# sram_rom_old.net
KiCad netlist of a schematic drawn in Altium Designer
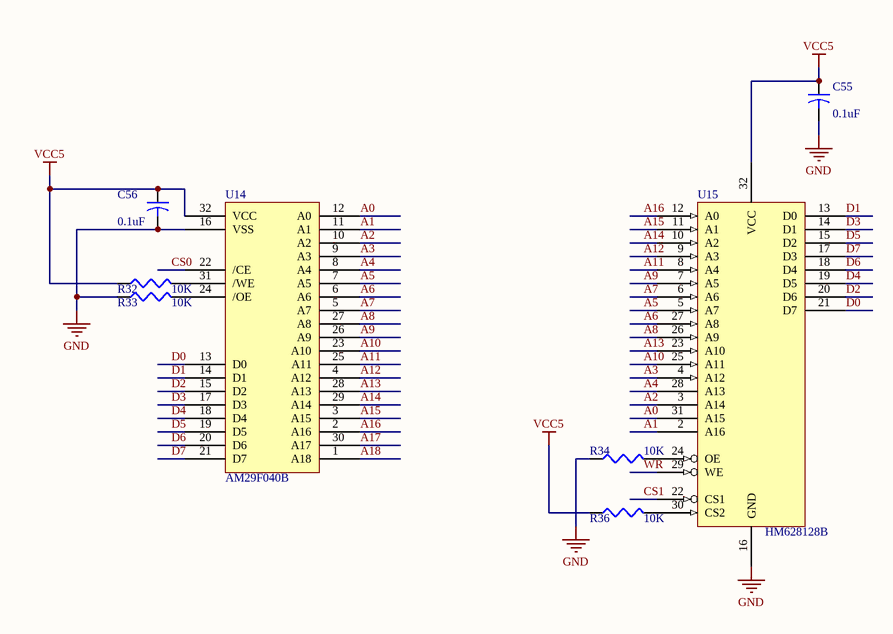
[diagram p0: sram_rom_old.SchDoc]

(export (version "E")
  (design (tool "Eeschema 10.0.6"))
  (components
    (comp (ref "C55")
      (value "0.1uF")
      (footprint "CAPC1608L")
      (description "Capacitor")
      (fields (field (name "Comment") "Cap2") (field (name "PUBLISHER") "Altium Limited"))
      (libsource (lib "Miscellaneous Devices") (part "Cap2"))
    )
    (comp (ref "C56")
      (value "0.1uF")
      (footprint "CAPC1608L")
      (description "Capacitor")
      (fields (field (name "Comment") "Cap2") (field (name "PUBLISHER") "Altium Limited"))
      (libsource (lib "Miscellaneous Devices") (part "Cap2"))
    )
    (comp (ref "R32")
      (value "10K")
      (footprint "RESC1608N")
      (description "Resistor")
      (fields (field (name "Comment") "Res3") (field (name "PUBLISHER") "Altium Limited"))
      (libsource (lib "Miscellaneous Devices") (part "Res3"))
    )
    (comp (ref "R33")
      (value "10K")
      (footprint "RESC1608N")
      (description "Resistor")
      (fields (field (name "Comment") "Res3") (field (name "PUBLISHER") "Altium Limited"))
      (libsource (lib "Miscellaneous Devices") (part "Res3"))
    )
    (comp (ref "R34")
      (value "10K")
      (footprint "RESC1608N")
      (description "Resistor")
      (fields (field (name "Comment") "Res3") (field (name "PUBLISHER") "Altium Limited"))
      (libsource (lib "Miscellaneous Devices") (part "Res3"))
    )
    (comp (ref "R36")
      (value "10K")
      (footprint "RESC1608N")
      (description "Resistor")
      (fields (field (name "Comment") "Res3") (field (name "PUBLISHER") "Altium Limited"))
      (libsource (lib "Miscellaneous Devices") (part "Res3"))
    )
    (comp (ref "U14")
      (value "AM29F040B")
      (footprint "PLCCS32")
      (description "512KBit x 8 ROM")
      (libsource (lib "ee52_tago_sch") (part "AM29F040B"))
    )
    (comp (ref "U15")
      (value "HM628128B")
      (footprint "DIP32")
      (description "1 M SRAM (128-kword x 8-bit)")
      (libsource (lib "eecs5x") (part "HM628128B"))
    )
  )
  (nets
    (net (code "1") (name "/A0") (class "Default")
      (node (ref "U14") (pin "12") (pinfunction "A0_12") (pintype "passive"))
      (node (ref "U15") (pin "31") (pinfunction "A15_31") (pintype "passive"))
    )
    (net (code "2") (name "/A1") (class "Default")
      (node (ref "U14") (pin "11") (pinfunction "A1_11") (pintype "passive"))
      (node (ref "U15") (pin "2") (pinfunction "A16_2") (pintype "passive"))
    )
    (net (code "3") (name "/A2") (class "Default")
      (node (ref "U14") (pin "10") (pinfunction "A2_10") (pintype "passive"))
      (node (ref "U15") (pin "3") (pinfunction "A14_3") (pintype "passive"))
    )
    (net (code "4") (name "/A3") (class "Default")
      (node (ref "U14") (pin "9") (pinfunction "A3_9") (pintype "passive"))
      (node (ref "U15") (pin "4") (pinfunction "A12_4") (pintype "input"))
    )
    (net (code "5") (name "/A4") (class "Default")
      (node (ref "U14") (pin "8") (pinfunction "A4_8") (pintype "passive"))
      (node (ref "U15") (pin "28") (pinfunction "A13_28") (pintype "passive"))
    )
    (net (code "6") (name "/A5") (class "Default")
      (node (ref "U14") (pin "7") (pinfunction "A5_7") (pintype "passive"))
      (node (ref "U15") (pin "5") (pinfunction "A7_5") (pintype "input"))
    )
    (net (code "7") (name "/A6") (class "Default")
      (node (ref "U14") (pin "6") (pinfunction "A6_6") (pintype "passive"))
      (node (ref "U15") (pin "27") (pinfunction "A8_27") (pintype "input"))
    )
    (net (code "8") (name "/A7") (class "Default")
      (node (ref "U14") (pin "5") (pinfunction "A7_5") (pintype "passive"))
      (node (ref "U15") (pin "6") (pinfunction "A6_6") (pintype "input"))
    )
    (net (code "9") (name "/A8") (class "Default")
      (node (ref "U14") (pin "27") (pinfunction "A8_27") (pintype "passive"))
      (node (ref "U15") (pin "26") (pinfunction "A9_26") (pintype "input"))
    )
    (net (code "10") (name "/A9") (class "Default")
      (node (ref "U14") (pin "26") (pinfunction "A9_26") (pintype "passive"))
      (node (ref "U15") (pin "7") (pinfunction "A5_7") (pintype "input"))
    )
    (net (code "11") (name "/A10") (class "Default")
      (node (ref "U14") (pin "23") (pinfunction "A10_23") (pintype "passive"))
      (node (ref "U15") (pin "25") (pinfunction "A11_25") (pintype "input"))
    )
    (net (code "12") (name "/A11") (class "Default")
      (node (ref "U14") (pin "25") (pinfunction "A11_25") (pintype "passive"))
      (node (ref "U15") (pin "8") (pinfunction "A4_8") (pintype "input"))
    )
    (net (code "13") (name "/A12") (class "Default")
      (node (ref "U14") (pin "4") (pinfunction "A12_4") (pintype "passive"))
      (node (ref "U15") (pin "9") (pinfunction "A3_9") (pintype "input"))
    )
    (net (code "14") (name "/A13") (class "Default")
      (node (ref "U14") (pin "28") (pinfunction "A13_28") (pintype "passive"))
      (node (ref "U15") (pin "23") (pinfunction "A10_23") (pintype "input"))
    )
    (net (code "15") (name "/A14") (class "Default")
      (node (ref "U14") (pin "29") (pinfunction "A14_29") (pintype "passive"))
      (node (ref "U15") (pin "10") (pinfunction "A2_10") (pintype "input"))
    )
    (net (code "16") (name "/A15") (class "Default")
      (node (ref "U14") (pin "3") (pinfunction "A15_3") (pintype "passive"))
      (node (ref "U15") (pin "11") (pinfunction "A1_11") (pintype "input"))
    )
    (net (code "17") (name "/A16") (class "Default")
      (node (ref "U14") (pin "2") (pinfunction "A16_2") (pintype "passive"))
      (node (ref "U15") (pin "12") (pinfunction "A0_12") (pintype "input"))
    )
    (net (code "18") (name "/A17") (class "Default")
      (node (ref "U14") (pin "30") (pinfunction "A17_30") (pintype "passive"))
    )
    (net (code "19") (name "/A18") (class "Default")
      (node (ref "U14") (pin "1") (pinfunction "A18_1") (pintype "passive"))
    )
    (net (code "20") (name "/CS0") (class "Default")
      (node (ref "U14") (pin "22") (pinfunction "/CE_22") (pintype "passive"))
    )
    (net (code "21") (name "/CS1") (class "Default")
      (node (ref "U15") (pin "22") (pinfunction "CS1_22") (pintype "input"))
    )
    (net (code "22") (name "/D0") (class "Default")
      (node (ref "U14") (pin "13") (pinfunction "D0_13") (pintype "passive"))
      (node (ref "U15") (pin "21") (pinfunction "D7_21") (pintype "tri_state"))
    )
    (net (code "23") (name "/D1") (class "Default")
      (node (ref "U14") (pin "14") (pinfunction "D1_14") (pintype "passive"))
      (node (ref "U15") (pin "13") (pinfunction "D0_13") (pintype "tri_state"))
    )
    (net (code "24") (name "/D2") (class "Default")
      (node (ref "U14") (pin "15") (pinfunction "D2_15") (pintype "passive"))
      (node (ref "U15") (pin "20") (pinfunction "D6_20") (pintype "tri_state"))
    )
    (net (code "25") (name "/D3") (class "Default")
      (node (ref "U14") (pin "17") (pinfunction "D3_17") (pintype "passive"))
      (node (ref "U15") (pin "14") (pinfunction "D1_14") (pintype "tri_state"))
    )
    (net (code "26") (name "/D4") (class "Default")
      (node (ref "U14") (pin "18") (pinfunction "D4_18") (pintype "passive"))
      (node (ref "U15") (pin "19") (pinfunction "D5_19") (pintype "tri_state"))
    )
    (net (code "27") (name "/D5") (class "Default")
      (node (ref "U14") (pin "19") (pinfunction "D5_19") (pintype "passive"))
      (node (ref "U15") (pin "15") (pinfunction "D2_15") (pintype "tri_state"))
    )
    (net (code "28") (name "/D6") (class "Default")
      (node (ref "U14") (pin "20") (pinfunction "D6_20") (pintype "passive"))
      (node (ref "U15") (pin "18") (pinfunction "D4_18") (pintype "tri_state"))
    )
    (net (code "29") (name "/D7") (class "Default")
      (node (ref "U14") (pin "21") (pinfunction "D7_21") (pintype "passive"))
      (node (ref "U15") (pin "17") (pinfunction "D3_17") (pintype "tri_state"))
    )
    (net (code "30") (name "/WR") (class "Default")
      (node (ref "U15") (pin "29") (pinfunction "WE_29") (pintype "input"))
    )
    (net (code "31") (name "GND") (class "Default")
      (node (ref "C55") (pin "2") (pinfunction "2_2") (pintype "passive"))
      (node (ref "C56") (pin "2") (pinfunction "2_2") (pintype "passive"))
      (node (ref "R33") (pin "1") (pinfunction "1_1") (pintype "passive"))
      (node (ref "R34") (pin "1") (pinfunction "1_1") (pintype "passive"))
      (node (ref "U14") (pin "16") (pinfunction "VSS_16") (pintype "passive"))
      (node (ref "U15") (pin "16") (pinfunction "GND_16") (pintype "power_in"))
    )
    (net (code "32") (name "Net-(U14-{slash}OE)") (class "Default")
      (node (ref "R33") (pin "2") (pinfunction "2_2") (pintype "passive"))
      (node (ref "U14") (pin "24") (pinfunction "/OE_24") (pintype "passive"))
    )
    (net (code "33") (name "Net-(U14-{slash}WE)") (class "Default")
      (node (ref "R32") (pin "2") (pinfunction "2_2") (pintype "passive"))
      (node (ref "U14") (pin "31") (pinfunction "/WE_31") (pintype "passive"))
    )
    (net (code "34") (name "Net-(U15-CS2)") (class "Default")
      (node (ref "R36") (pin "2") (pinfunction "2_2") (pintype "passive"))
      (node (ref "U15") (pin "30") (pinfunction "CS2_30") (pintype "input"))
    )
    (net (code "35") (name "Net-(U15-OE)") (class "Default")
      (node (ref "R34") (pin "2") (pinfunction "2_2") (pintype "passive"))
      (node (ref "U15") (pin "24") (pinfunction "OE_24") (pintype "input"))
    )
    (net (code "36") (name "VCC5") (class "Default")
      (node (ref "C55") (pin "1") (pinfunction "1_1") (pintype "passive"))
      (node (ref "C56") (pin "1") (pinfunction "1_1") (pintype "passive"))
      (node (ref "R32") (pin "1") (pinfunction "1_1") (pintype "passive"))
      (node (ref "R36") (pin "1") (pinfunction "1_1") (pintype "passive"))
      (node (ref "U14") (pin "32") (pinfunction "VCC_32") (pintype "passive"))
      (node (ref "U15") (pin "32") (pinfunction "VCC_32") (pintype "power_in"))
    )
  )
)
